# MCU_SLAVES.net
KiCad netlist of a schematic drawn in Altium Designer
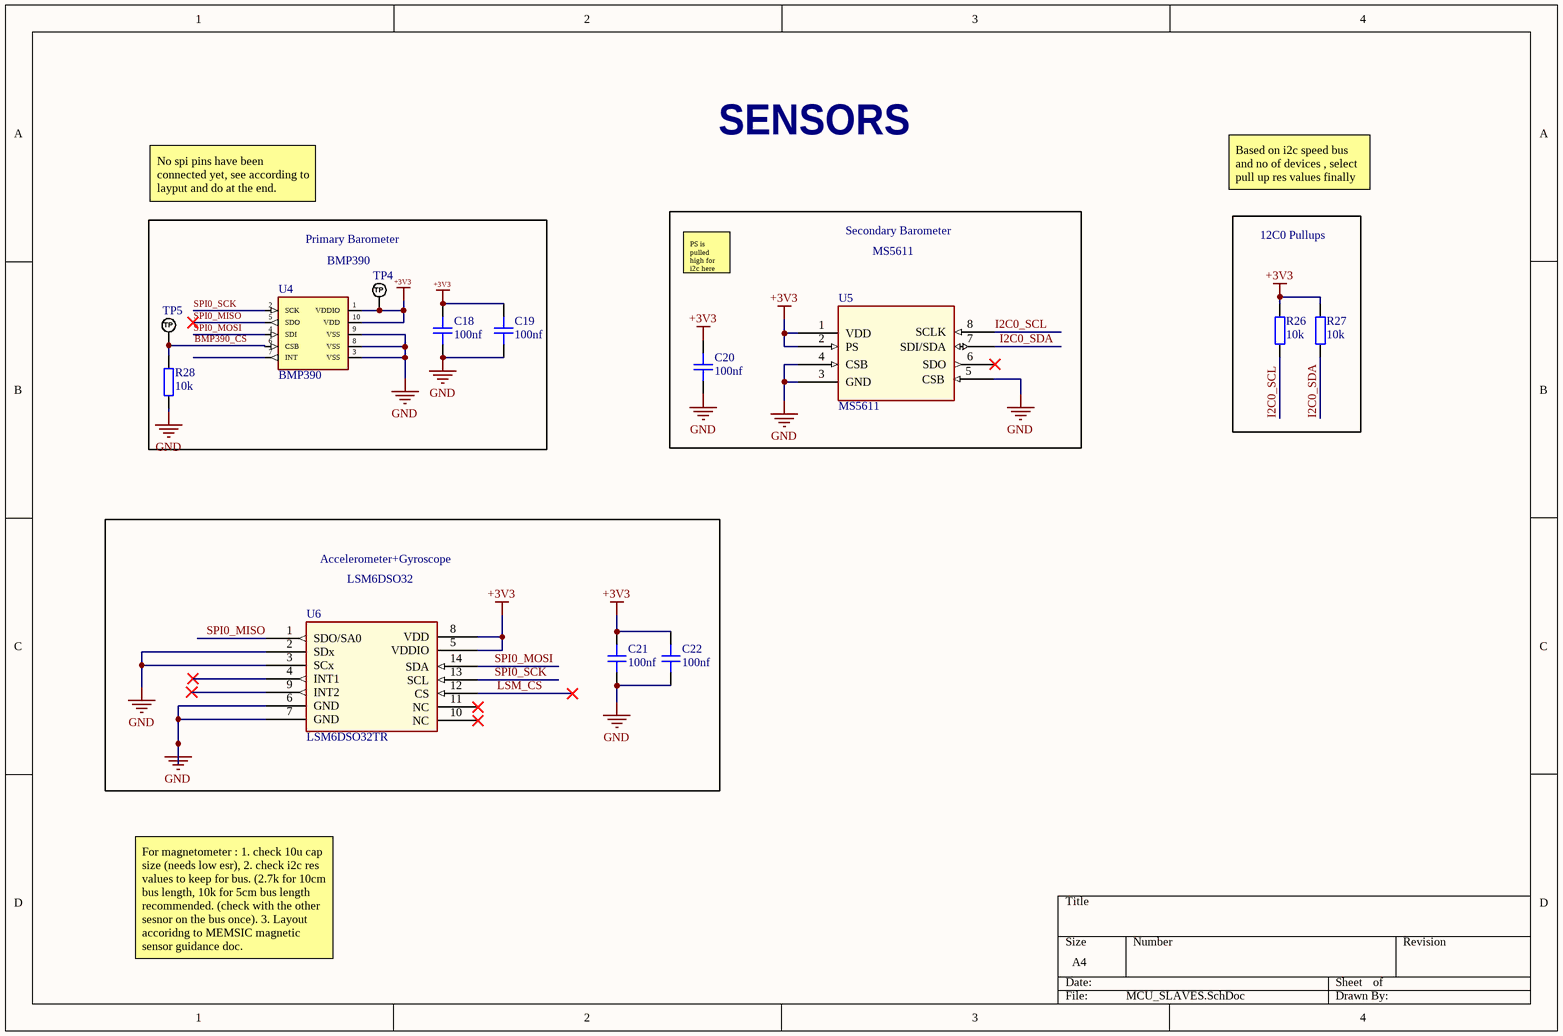
[diagram p0: MCU_SLAVES.SchDoc]

(export (version "E")
  (design (tool "Eeschema 10.0.6"))
  (components
    (comp (ref "C18")
      (value "100nf")
      (footprint "CAP_0402")
      (description "Capacitor SMD 0402")
      (libsource (lib "SchematicSchlib1") (part "CAP_0402"))
    )
    (comp (ref "C19")
      (value "100nf")
      (footprint "CAP_0402")
      (description "Capacitor SMD 0402")
      (libsource (lib "SchematicSchlib1") (part "CAP_0402"))
    )
    (comp (ref "C20")
      (value "100nf")
      (footprint "CAP_0402")
      (description "Capacitor SMD 0402")
      (libsource (lib "SchematicSchlib1") (part "CAP_0402"))
    )
    (comp (ref "C21")
      (value "100nf")
      (footprint "CAP_0402")
      (description "Capacitor SMD 0402")
      (libsource (lib "SchematicSchlib1") (part "CAP_0402"))
    )
    (comp (ref "C22")
      (value "100nf")
      (footprint "CAP_0402")
      (description "Capacitor SMD 0402")
      (libsource (lib "SchematicSchlib1") (part "CAP_0402"))
    )
    (comp (ref "R26")
      (value "10k")
      (footprint "RES_0402")
      (description "Resistor SMD 0402")
      (libsource (lib "SchematicSchlib1") (part "RES_0402"))
    )
    (comp (ref "R27")
      (value "10k")
      (footprint "RES_0402")
      (description "Resistor SMD 0402")
      (libsource (lib "SchematicSchlib1") (part "RES_0402"))
    )
    (comp (ref "R28")
      (value "10k")
      (footprint "RES_0402")
      (description "Resistor SMD 0402")
      (libsource (lib "SchematicSchlib1") (part "RES_0402"))
    )
    (comp (ref "TP4")
      (value "TEST_POINT_RND_1MM")
      (footprint "PAD_RND_1MM")
      (description "Test Point Round 1mm (NO BOM)")
      (fields (field (name "SOURCE") "Schematic-Lib-PhilsLab.SchLib"))
      (libsource (lib "Shravan Talapady") (part "TEST_POINT_RND_1MM"))
    )
    (comp (ref "TP5")
      (value "TEST_POINT_RND_1MM")
      (footprint "PAD_RND_1MM")
      (description "Test Point Round 1mm (NO BOM)")
      (fields (field (name "SOURCE") "Schematic-Lib-PhilsLab.SchLib"))
      (libsource (lib "Shravan Talapady") (part "TEST_POINT_RND_1MM"))
    )
    (comp (ref "U4")
      (value "BMP390")
      (footprint "BMP390")
      (libsource (lib "SchematicSchlib1") (part "BMP390"))
    )
    (comp (ref "U5")
      (value "MS5611")
      (footprint "MS5611")
      (libsource (lib "SchematicSchlib1") (part "MS5611"))
    )
    (comp (ref "U6")
      (value "LSM6DSO32TR")
      (footprint "LSM6DSO32TR")
      (libsource (lib "SchematicSchlib1") (part "LSM6DSO32TR"))
    )
  )
  (nets
    (net (code "1") (name "+3V3") (class "Default")
      (node (ref "C18") (pin "2") (pinfunction "2_2") (pintype "passive"))
      (node (ref "C19") (pin "2") (pinfunction "2_2") (pintype "passive"))
      (node (ref "C20") (pin "2") (pinfunction "2_2") (pintype "passive"))
      (node (ref "C21") (pin "2") (pinfunction "2_2") (pintype "passive"))
      (node (ref "C22") (pin "1") (pinfunction "1_1") (pintype "passive"))
      (node (ref "R26") (pin "2") (pinfunction "2_2") (pintype "passive"))
      (node (ref "R27") (pin "2") (pinfunction "2_2") (pintype "passive"))
      (node (ref "TP4") (pin "1") (pinfunction "TP_1") (pintype "passive"))
      (node (ref "U4") (pin "1") (pinfunction "VDDIO_1") (pintype "power_in"))
      (node (ref "U4") (pin "10") (pinfunction "VDD_10") (pintype "power_in"))
      (node (ref "U5") (pin "1") (pinfunction "VDD_1") (pintype "power_in"))
      (node (ref "U5") (pin "2") (pinfunction "PS_2") (pintype "input"))
      (node (ref "U6") (pin "5") (pinfunction "VDDIO_5") (pintype "power_in"))
      (node (ref "U6") (pin "8") (pinfunction "VDD_8") (pintype "power_in"))
    )
    (net (code "2") (name "/BMP390_CS") (class "Default")
      (node (ref "R28") (pin "2") (pinfunction "2_2") (pintype "passive"))
      (node (ref "TP5") (pin "1") (pinfunction "TP_1") (pintype "passive"))
      (node (ref "U4") (pin "6") (pinfunction "CSB_6") (pintype "input"))
    )
    (net (code "3") (name "/I2C0_SCL") (class "Default")
      (node (ref "R26") (pin "1") (pinfunction "1_1") (pintype "passive"))
      (node (ref "U5") (pin "8") (pinfunction "SCLK_8") (pintype "input"))
    )
    (net (code "4") (name "/I2C0_SDA") (class "Default")
      (node (ref "R27") (pin "1") (pinfunction "1_1") (pintype "passive"))
      (node (ref "U5") (pin "7") (pinfunction "SDI/SDA_7") (pintype "bidirectional"))
    )
    (net (code "5") (name "/LSM_CS") (class "Default")
      (node (ref "U6") (pin "12") (pinfunction "CS_12") (pintype "input+no_connect"))
    )
    (net (code "6") (name "/SPI0_MISO") (class "Default")
      (node (ref "U4") (pin "5") (pinfunction "SDO_5") (pintype "output"))
      (node (ref "U6") (pin "1") (pinfunction "SDO/SA0_1") (pintype "output"))
    )
    (net (code "7") (name "/SPI0_MOSI") (class "Default")
      (node (ref "U4") (pin "4") (pinfunction "SDI_4") (pintype "input"))
      (node (ref "U6") (pin "14") (pinfunction "SDA_14") (pintype "input"))
    )
    (net (code "8") (name "/SPI0_SCK") (class "Default")
      (node (ref "U4") (pin "2") (pinfunction "SCK_2") (pintype "input"))
      (node (ref "U6") (pin "13") (pinfunction "SCL_13") (pintype "input"))
    )
    (net (code "9") (name "GND") (class "Default")
      (node (ref "C18") (pin "1") (pinfunction "1_1") (pintype "passive"))
      (node (ref "C19") (pin "1") (pinfunction "1_1") (pintype "passive"))
      (node (ref "C20") (pin "1") (pinfunction "1_1") (pintype "passive"))
      (node (ref "C21") (pin "1") (pinfunction "1_1") (pintype "passive"))
      (node (ref "C22") (pin "2") (pinfunction "2_2") (pintype "passive"))
      (node (ref "R28") (pin "1") (pinfunction "1_1") (pintype "passive"))
      (node (ref "U4") (pin "3") (pinfunction "VSS_3") (pintype "power_in"))
      (node (ref "U4") (pin "8") (pinfunction "VSS_8") (pintype "power_in"))
      (node (ref "U4") (pin "9") (pinfunction "VSS_9") (pintype "power_in"))
      (node (ref "U5") (pin "3") (pinfunction "GND_3") (pintype "power_in"))
      (node (ref "U5") (pin "4") (pinfunction "CSB_4") (pintype "input"))
      (node (ref "U5") (pin "5") (pinfunction "CSB_5") (pintype "input"))
      (node (ref "U6") (pin "2") (pinfunction "SDx_2") (pintype "passive"))
      (node (ref "U6") (pin "3") (pinfunction "SCx_3") (pintype "passive"))
      (node (ref "U6") (pin "6") (pinfunction "GND_6") (pintype "power_in"))
      (node (ref "U6") (pin "7") (pinfunction "GND_7") (pintype "power_in"))
    )
    (net (code "10") (name "unconnected-(U4-INT-Pad7)") (class "Default")
      (node (ref "U4") (pin "7") (pinfunction "INT_7") (pintype "output"))
    )
    (net (code "11") (name "unconnected-(U5-SDO-Pad6)") (class "Default")
      (node (ref "U5") (pin "6") (pinfunction "SDO_6") (pintype "output+no_connect"))
    )
    (net (code "12") (name "unconnected-(U6-INT1-Pad4)") (class "Default")
      (node (ref "U6") (pin "4") (pinfunction "INT1_4") (pintype "output+no_connect"))
    )
    (net (code "13") (name "unconnected-(U6-INT2-Pad9)") (class "Default")
      (node (ref "U6") (pin "9") (pinfunction "INT2_9") (pintype "output+no_connect"))
    )
    (net (code "14") (name "unconnected-(U6-NC-Pad10)") (class "Default")
      (node (ref "U6") (pin "10") (pinfunction "NC_10") (pintype "passive+no_connect"))
    )
    (net (code "15") (name "unconnected-(U6-NC-Pad11)") (class "Default")
      (node (ref "U6") (pin "11") (pinfunction "NC_11") (pintype "passive+no_connect"))
    )
  )
)
